# fonte_simoes.net
KiCad netlist of a schematic drawn in EAGLE
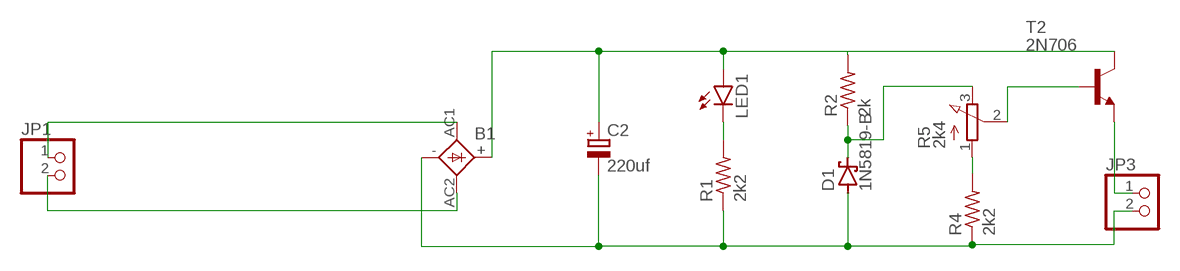
[diagram p0: schematic, sheet 1]

(export (version "E")
  (design (tool "Eeschema 10.0.6"))
  (components
    (comp (ref "B1")
      (value "1KAB")
      (footprint "eagle-import:1KAB")
      (libsource (lib "eagle-import") (part "1KAB"))
    )
    (comp (ref "C2")
      (value "220uf")
      (footprint "eagle-import:TT5D10")
      (libsource (lib "eagle-import") (part "CPOL-EUTT5D10"))
    )
    (comp (ref "D1")
      (value "1N5819-B")
      (footprint "eagle-import:DO41-7.6")
      (libsource (lib "eagle-import") (part "1N5819-B"))
    )
    (comp (ref "JP1")
      (value "PINHD-1X2")
      (footprint "eagle-import:1X02")
      (libsource (lib "eagle-import") (part "PINHD-1X2"))
    )
    (comp (ref "JP3")
      (value "PINHD-1X2")
      (footprint "eagle-import:1X02")
      (libsource (lib "eagle-import") (part "PINHD-1X2"))
    )
    (comp (ref "LED1")
      (value "LED5MM")
      (footprint "eagle-import:LED5MM")
      (libsource (lib "eagle-import") (part "LED5MM"))
    )
    (comp (ref "R1")
      (value "2k2")
      (footprint "eagle-import:0309_12")
      (libsource (lib "eagle-import") (part "R-US_0309/12"))
    )
    (comp (ref "R2")
      (value "2k")
      (footprint "eagle-import:0309_12")
      (libsource (lib "eagle-import") (part "R-US_0309/12"))
    )
    (comp (ref "R4")
      (value "2k2")
      (footprint "eagle-import:0309_12")
      (libsource (lib "eagle-import") (part "R-US_0309/12"))
    )
    (comp (ref "R5")
      (value "2k4")
      (footprint "eagle-import:3RP_1610N")
      (libsource (lib "eagle-import") (part "3RP/1610N"))
    )
    (comp (ref "T2")
      (value "2N706")
      (footprint "eagle-import:TO18")
      (libsource (lib "eagle-import") (part "2N706"))
    )
  )
  (nets
    (net (code "1") (name "Net-(B1-Pad-)") (class "Default")
      (node (ref "B1") (pin "-") (pinfunction "-_-") (pintype "passive"))
      (node (ref "C2") (pin "-") (pinfunction "-_-") (pintype "passive"))
      (node (ref "D1") (pin "A") (pinfunction "A_A") (pintype "passive"))
      (node (ref "JP3") (pin "2") (pinfunction "2_2") (pintype "passive"))
      (node (ref "R1") (pin "1") (pinfunction "1_1") (pintype "passive"))
      (node (ref "R4") (pin "1") (pinfunction "1_1") (pintype "passive"))
    )
    (net (code "2") (name "Net-(B1-PadAC1)") (class "Default")
      (node (ref "B1") (pin "AC1") (pinfunction "AC1_AC1") (pintype "passive"))
      (node (ref "JP1") (pin "1") (pinfunction "1_1") (pintype "passive"))
    )
    (net (code "3") (name "Net-(B1-PadAC2)") (class "Default")
      (node (ref "B1") (pin "AC2") (pinfunction "AC2_AC2") (pintype "passive"))
      (node (ref "JP1") (pin "2") (pinfunction "2_2") (pintype "passive"))
    )
    (net (code "4") (name "Net-(LED1-C)") (class "Default")
      (node (ref "LED1") (pin "K") (pinfunction "C_K") (pintype "passive"))
      (node (ref "R1") (pin "2") (pinfunction "2_2") (pintype "passive"))
    )
    (net (code "5") (name "Net-(R5-A)") (class "Default")
      (node (ref "R4") (pin "2") (pinfunction "2_2") (pintype "passive"))
      (node (ref "R5") (pin "1") (pinfunction "A_1") (pintype "passive"))
    )
    (net (code "6") (name "Net-(R5-E)") (class "Default")
      (node (ref "D1") (pin "C") (pinfunction "C_C") (pintype "passive"))
      (node (ref "R2") (pin "1") (pinfunction "1_1") (pintype "passive"))
      (node (ref "R5") (pin "3") (pinfunction "E_3") (pintype "passive"))
    )
    (net (code "7") (name "Net-(R5-S)") (class "Default")
      (node (ref "R5") (pin "2") (pinfunction "S_2") (pintype "passive"))
      (node (ref "T2") (pin "2") (pinfunction "B_2") (pintype "passive"))
    )
    (net (code "8") (name "Net-(T2-C)") (class "Default")
      (node (ref "B1") (pin "+") (pinfunction "+_+") (pintype "passive"))
      (node (ref "C2") (pin "+") (pinfunction "+_+") (pintype "passive"))
      (node (ref "LED1") (pin "A") (pinfunction "A_A") (pintype "passive"))
      (node (ref "R2") (pin "2") (pinfunction "2_2") (pintype "passive"))
      (node (ref "T2") (pin "3") (pinfunction "C_3") (pintype "passive"))
    )
    (net (code "9") (name "Net-(T2-E)") (class "Default")
      (node (ref "JP3") (pin "1") (pinfunction "1_1") (pintype "passive"))
      (node (ref "T2") (pin "1") (pinfunction "E_1") (pintype "passive"))
    )
  )
)
